# DongHoInternet.net
KiCad netlist of a schematic drawn in Altium Designer
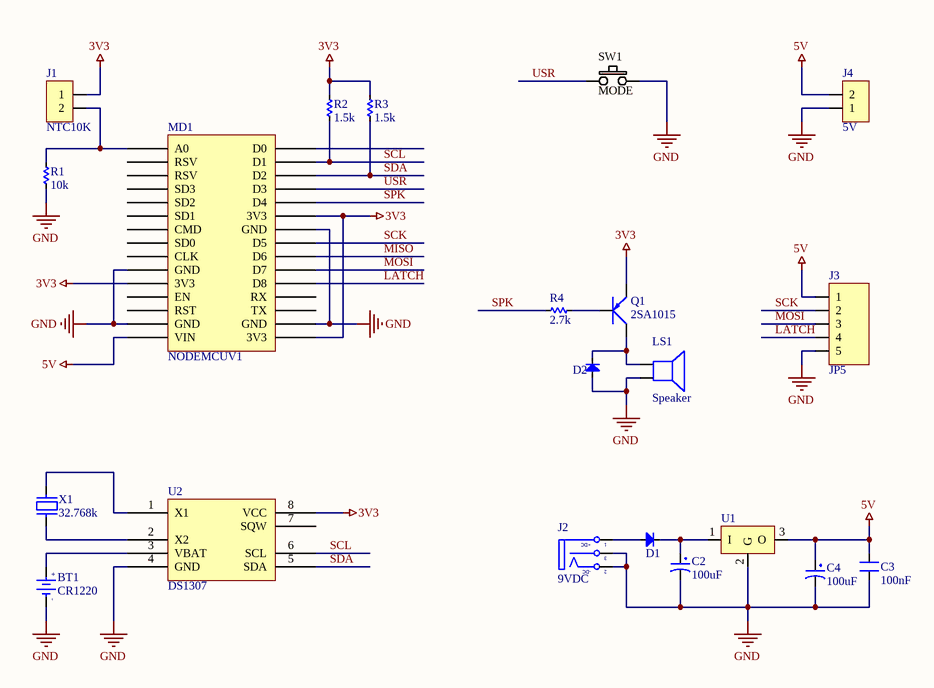
[diagram p0: DongHoInternet.SchDoc]

(export (version "E")
  (design (tool "Eeschema 10.0.6"))
  (components
    (comp (ref "BT1") (value "CR1220") (footprint "PIN CR1220") (libsource (lib "User1") (part "PIN CR1220")))
    (comp (ref "C2")
      (value "100uF")
      (footprint "TU TANTALUM")
      (libsource (lib "User1") (part "CAP TANTALUM"))
    )
    (comp (ref "C3") (value "100nF") (footprint "CN-SMD-0805") (libsource (lib "LIBRARY") (part "CN")))
    (comp (ref "C4")
      (value "100uF")
      (footprint "TU TANTALUM")
      (libsource (lib "User1") (part "CAP TANTALUM"))
    )
    (comp (ref "D1")
      (value "Diode SMD")
      (footprint "DIO-SMD-106")
      (description "Default Diode")
      (fields (field (name "PUBLISHER") "Altium Limited"))
      (libsource (lib "LIBRARY") (part "Diode SMD"))
    )
    (comp (ref "D2")
      (value "Diode SMD")
      (footprint "DIO-SMD-106")
      (description "Default Diode")
      (fields (field (name "PUBLISHER") "Altium Limited"))
      (libsource (lib "LIBRARY") (part "Diode SMD"))
    )
    (comp (ref "J1")
      (value "NTC10K")
      (footprint "JP2-D1T")
      (description "WR-PHD 2.54 mm Angled Socket Header")
      (fields
        (field (name "MANUFACTURER") "Würth Elektronik eiSos GmbH")
        (field (name "PARTNO") "613002143121")
        (field (name "CREATED BY") "Karrer Zheng")
      )
      (libsource (lib "LIBRARY") (part "JP2"))
    )
    (comp (ref "J2")
      (value "9VDC")
      (footprint "DC0")
      (description "Jac DC input")
      (libsource (lib "LIBRARY") (part "DCIN"))
    )
    (comp (ref "J3")
      (value "JP5")
      (footprint "JP5-D1C")
      (description "WR-PHD 2.54 mm Angled Socket Header")
      (fields
        (field (name "MANUFACTURER") "Würth Elektronik eiSos GmbH")
        (field (name "PARTNO") "613005143121")
        (field (name "CREATED BY") "Karrer Zheng")
      )
      (libsource (lib "LIBRARY") (part "JP5"))
    )
    (comp (ref "J4")
      (value "5V")
      (footprint "JP2-D1C")
      (description "WR-PHD 2.54 mm Angled Socket Header")
      (fields
        (field (name "MANUFACTURER") "Würth Elektronik eiSos GmbH")
        (field (name "PARTNO") "613002143121")
        (field (name "CREATED BY") "Karrer Zheng")
      )
      (libsource (lib "") (part "JP2_1"))
    )
    (comp (ref "LS1")
      (value "Speaker")
      (footprint "SPEAKER")
      (description "Loudspeaker")
      (fields (field (name "PUBLISHER") "Altium Limited"))
      (libsource (lib "LIBRARY") (part "Speaker"))
    )
    (comp (ref "MD1") (value "NODEMCUV1") (footprint "NODEMCUV1") (libsource (lib "User") (part "NODEMCUV1")))
    (comp (ref "Q1")
      (value "2SA1015")
      (footprint "SOT23-321")
      (description "PNP 600mW, ECB")
      (libsource (lib "LIBRARY") (part "2SA1015"))
    )
    (comp (ref "R1")
      (value "10k")
      (footprint "RES-SMD-0805")
      (description "Resistor")
      (fields
        (field (name "MANUFACTURER") "Generic Components")
        (field (name "PUBLISHER") "Altium Hobart Technology Centre")
      )
      (libsource (lib "LIBRARY") (part "Res-SMD"))
    )
    (comp (ref "R2")
      (value "1.5k")
      (footprint "RES-SMD-0805")
      (description "Resistor")
      (fields
        (field (name "MANUFACTURER") "Generic Components")
        (field (name "PUBLISHER") "Altium Hobart Technology Centre")
      )
      (libsource (lib "LIBRARY") (part "Res-SMD"))
    )
    (comp (ref "R3")
      (value "1.5k")
      (footprint "RES-SMD-0805")
      (description "Resistor")
      (fields
        (field (name "MANUFACTURER") "Generic Components")
        (field (name "PUBLISHER") "Altium Hobart Technology Centre")
      )
      (libsource (lib "LIBRARY") (part "Res-SMD"))
    )
    (comp (ref "R4")
      (value "2.7k")
      (footprint "RES-SMD-0805")
      (description "Resistor")
      (fields
        (field (name "MANUFACTURER") "Generic Components")
        (field (name "PUBLISHER") "Altium Hobart Technology Centre")
      )
      (libsource (lib "LIBRARY") (part "Res-SMD"))
    )
    (comp (ref "SW1")
      (value "MODE")
      (footprint "SW-OMRONRA-Y")
      (description "SW-D6-R / SW-DS-S / SW-14X14 / SW-7X7")
      (libsource (lib "vh_altium_library") (part "SW-PB-YELLOW-RA"))
    )
    (comp (ref "U1")
      (value "LM78xx")
      (footprint "TO252-123")
      (description "Positive Voltage Regulator")
      (fields (field (name "PUBLISHER") "Altium Limited"))
      (libsource (lib "LIBRARY") (part "LM78xx"))
    )
    (comp (ref "U2") (value "DS1307") (footprint "DS1307") (libsource (lib "User2") (part "DS1307")))
    (comp (ref "X1")
      (value "32.768k")
      (footprint "XT32k")
      (description "Crystal, 32.768 KHz, -40 to 85 degC, 3.2 x 1.5 x 0.9 mm SMD")
      (libsource (lib "LIBRARY") (part "XT2"))
    )
  )
  (nets
    (net (code "1") (name "/LATCH") (class "Default")
      (node (ref "J3") (pin "4") (pinfunction "4_4") (pintype "passive"))
      (node (ref "MD1") (pin "D8") (pinfunction "D8_D8") (pintype "passive"))
    )
    (net (code "2") (name "/MISO") (class "Default")
      (node (ref "MD1") (pin "D6") (pinfunction "D6_D6") (pintype "passive"))
    )
    (net (code "3") (name "/MOSI") (class "Default")
      (node (ref "J3") (pin "3") (pinfunction "3_3") (pintype "passive"))
      (node (ref "MD1") (pin "D7") (pinfunction "D7_D7") (pintype "passive"))
    )
    (net (code "4") (name "/SCK") (class "Default")
      (node (ref "J3") (pin "2") (pinfunction "2_2") (pintype "passive"))
      (node (ref "MD1") (pin "D5") (pinfunction "D5_D5") (pintype "passive"))
    )
    (net (code "5") (name "/SCL") (class "Default")
      (node (ref "MD1") (pin "D1") (pinfunction "D1_D1") (pintype "passive"))
      (node (ref "R2") (pin "2") (pinfunction "2_2") (pintype "passive"))
      (node (ref "U2") (pin "6") (pinfunction "SCL_6") (pintype "passive"))
    )
    (net (code "6") (name "/SDA") (class "Default")
      (node (ref "MD1") (pin "D2") (pinfunction "D2_D2") (pintype "passive"))
      (node (ref "R3") (pin "2") (pinfunction "2_2") (pintype "passive"))
      (node (ref "U2") (pin "5") (pinfunction "SDA_5") (pintype "passive"))
    )
    (net (code "7") (name "/SPK") (class "Default")
      (node (ref "MD1") (pin "D4") (pinfunction "D4_D4") (pintype "passive"))
      (node (ref "R4") (pin "1") (pinfunction "1_1") (pintype "passive"))
    )
    (net (code "8") (name "/USR") (class "Default")
      (node (ref "MD1") (pin "D3") (pinfunction "D3_D3") (pintype "passive"))
      (node (ref "SW1") (pin "2") (pintype "passive"))
    )
    (net (code "9") (name "3V3") (class "Default")
      (node (ref "J1") (pin "1") (pinfunction "1_1") (pintype "passive"))
      (node (ref "MD1") (pin "3V3") (pinfunction "3V3_3V3") (pintype "passive"))
      (node (ref "Q1") (pin "1") (pinfunction "E_1") (pintype "passive"))
      (node (ref "R2") (pin "1") (pinfunction "1_1") (pintype "passive"))
      (node (ref "R3") (pin "1") (pinfunction "1_1") (pintype "passive"))
      (node (ref "U2") (pin "8") (pinfunction "VCC_8") (pintype "passive"))
    )
    (net (code "10") (name "5V") (class "Default")
      (node (ref "C3") (pin "2") (pinfunction "2_2") (pintype "passive"))
      (node (ref "C4") (pin "1") (pinfunction "1_1") (pintype "passive"))
      (node (ref "J3") (pin "1") (pinfunction "1_1") (pintype "passive"))
      (node (ref "J4") (pin "2") (pinfunction "2_2") (pintype "passive"))
      (node (ref "MD1") (pin "VIN") (pinfunction "VIN_VIN") (pintype "passive"))
      (node (ref "U1") (pin "3") (pinfunction "O_3") (pintype "power_in"))
    )
    (net (code "11") (name "GND") (class "Default")
      (node (ref "BT1") (pin "2") (pinfunction "GND_2") (pintype "passive"))
      (node (ref "C2") (pin "2") (pinfunction "2_2") (pintype "passive"))
      (node (ref "C3") (pin "1") (pinfunction "1_1") (pintype "passive"))
      (node (ref "C4") (pin "2") (pinfunction "2_2") (pintype "passive"))
      (node (ref "D2") (pin "1") (pinfunction "A_1") (pintype "passive"))
      (node (ref "J2") (pin "2") (pinfunction "TN_2") (pintype "passive"))
      (node (ref "J2") (pin "3") (pinfunction "S_3") (pintype "power_in"))
      (node (ref "J3") (pin "5") (pinfunction "5_5") (pintype "passive"))
      (node (ref "J4") (pin "1") (pinfunction "1_1") (pintype "passive"))
      (node (ref "LS1") (pin "2") (pinfunction "2_2") (pintype "passive"))
      (node (ref "MD1") (pin "GND") (pinfunction "GND_GND") (pintype "passive"))
      (node (ref "R1") (pin "2") (pinfunction "2_2") (pintype "passive"))
      (node (ref "SW1") (pin "1") (pintype "passive"))
      (node (ref "U1") (pin "2") (pinfunction "G_2") (pintype "power_in"))
      (node (ref "U2") (pin "4") (pinfunction "GND_4") (pintype "passive"))
    )
    (net (code "12") (name "Net-(BT1-+3V)") (class "Default")
      (node (ref "BT1") (pin "1") (pinfunction "+3V_1") (pintype "passive"))
      (node (ref "U2") (pin "3") (pinfunction "VBAT_3") (pintype "passive"))
    )
    (net (code "13") (name "Net-(D1-A)") (class "Default")
      (node (ref "D1") (pin "1") (pinfunction "A_1") (pintype "passive"))
      (node (ref "J2") (pin "1") (pinfunction "T_1") (pintype "passive"))
    )
    (net (code "14") (name "Net-(D1-K)") (class "Default")
      (node (ref "C2") (pin "1") (pinfunction "1_1") (pintype "passive"))
      (node (ref "D1") (pin "2") (pinfunction "K_2") (pintype "passive"))
      (node (ref "U1") (pin "1") (pinfunction "I_1") (pintype "power_in"))
    )
    (net (code "15") (name "Net-(D2-K)") (class "Default")
      (node (ref "D2") (pin "2") (pinfunction "K_2") (pintype "passive"))
      (node (ref "LS1") (pin "1") (pinfunction "1_1") (pintype "passive"))
      (node (ref "Q1") (pin "2") (pinfunction "C_2") (pintype "passive"))
    )
    (net (code "16") (name "Net-(J1-Pad2)") (class "Default")
      (node (ref "J1") (pin "2") (pinfunction "2_2") (pintype "passive"))
      (node (ref "MD1") (pin "A0") (pinfunction "A0_A0") (pintype "passive"))
      (node (ref "R1") (pin "1") (pinfunction "1_1") (pintype "passive"))
    )
    (net (code "17") (name "Net-(Q1-B)") (class "Default")
      (node (ref "Q1") (pin "3") (pinfunction "B_3") (pintype "passive"))
      (node (ref "R4") (pin "2") (pinfunction "2_2") (pintype "passive"))
    )
    (net (code "18") (name "Net-(U2-X1)") (class "Default")
      (node (ref "U2") (pin "1") (pinfunction "X1_1") (pintype "passive"))
      (node (ref "X1") (pin "2") (pinfunction "2_2") (pintype "passive"))
    )
    (net (code "19") (name "Net-(U2-X2)") (class "Default")
      (node (ref "U2") (pin "2") (pinfunction "X2_2") (pintype "passive"))
      (node (ref "X1") (pin "1") (pinfunction "1_1") (pintype "passive"))
    )
    (net (code "20") (name "unconnected-(MD1-PadCLK)") (class "Default")
      (node (ref "MD1") (pin "CLK") (pinfunction "CLK_CLK") (pintype "passive"))
    )
    (net (code "21") (name "unconnected-(MD1-PadCMD)") (class "Default")
      (node (ref "MD1") (pin "CMD") (pinfunction "CMD_CMD") (pintype "passive"))
    )
    (net (code "22") (name "unconnected-(MD1-PadD0)") (class "Default")
      (node (ref "MD1") (pin "D0") (pinfunction "D0_D0") (pintype "passive"))
    )
    (net (code "23") (name "unconnected-(MD1-PadEN)") (class "Default")
      (node (ref "MD1") (pin "EN") (pinfunction "EN_EN") (pintype "passive"))
    )
    (net (code "24") (name "unconnected-(MD1-PadRST)") (class "Default")
      (node (ref "MD1") (pin "RST") (pinfunction "RST_RST") (pintype "passive"))
    )
    (net (code "25") (name "unconnected-(MD1-PadRSV)") (class "Default")
      (node (ref "MD1") (pin "RSV") (pinfunction "RSV_RSV") (pintype "passive"))
    )
    (net (code "26") (name "unconnected-(MD1-PadRSV)_1") (class "Default")
      (node (ref "MD1") (pin "RSV") (pinfunction "RSV_RSV") (pintype "passive"))
    )
    (net (code "27") (name "unconnected-(MD1-PadRX)") (class "Default")
      (node (ref "MD1") (pin "RX") (pinfunction "RX_RX") (pintype "passive"))
    )
    (net (code "28") (name "unconnected-(MD1-PadSD0)") (class "Default")
      (node (ref "MD1") (pin "SD0") (pinfunction "SD0_SD0") (pintype "passive"))
    )
    (net (code "29") (name "unconnected-(MD1-PadSD1)") (class "Default")
      (node (ref "MD1") (pin "SD1") (pinfunction "SD1_SD1") (pintype "passive"))
    )
    (net (code "30") (name "unconnected-(MD1-PadSD2)") (class "Default")
      (node (ref "MD1") (pin "SD2") (pinfunction "SD2_SD2") (pintype "passive"))
    )
    (net (code "31") (name "unconnected-(MD1-PadSD3)") (class "Default")
      (node (ref "MD1") (pin "SD3") (pinfunction "SD3_SD3") (pintype "passive"))
    )
    (net (code "32") (name "unconnected-(MD1-PadTX)") (class "Default")
      (node (ref "MD1") (pin "TX") (pinfunction "TX_TX") (pintype "passive"))
    )
    (net (code "33") (name "unconnected-(U2-SQW-Pad7)") (class "Default")
      (node (ref "U2") (pin "7") (pinfunction "SQW_7") (pintype "passive"))
    )
  )
)
